# Buzzer_imp.net
KiCad netlist of a schematic drawn in EAGLE
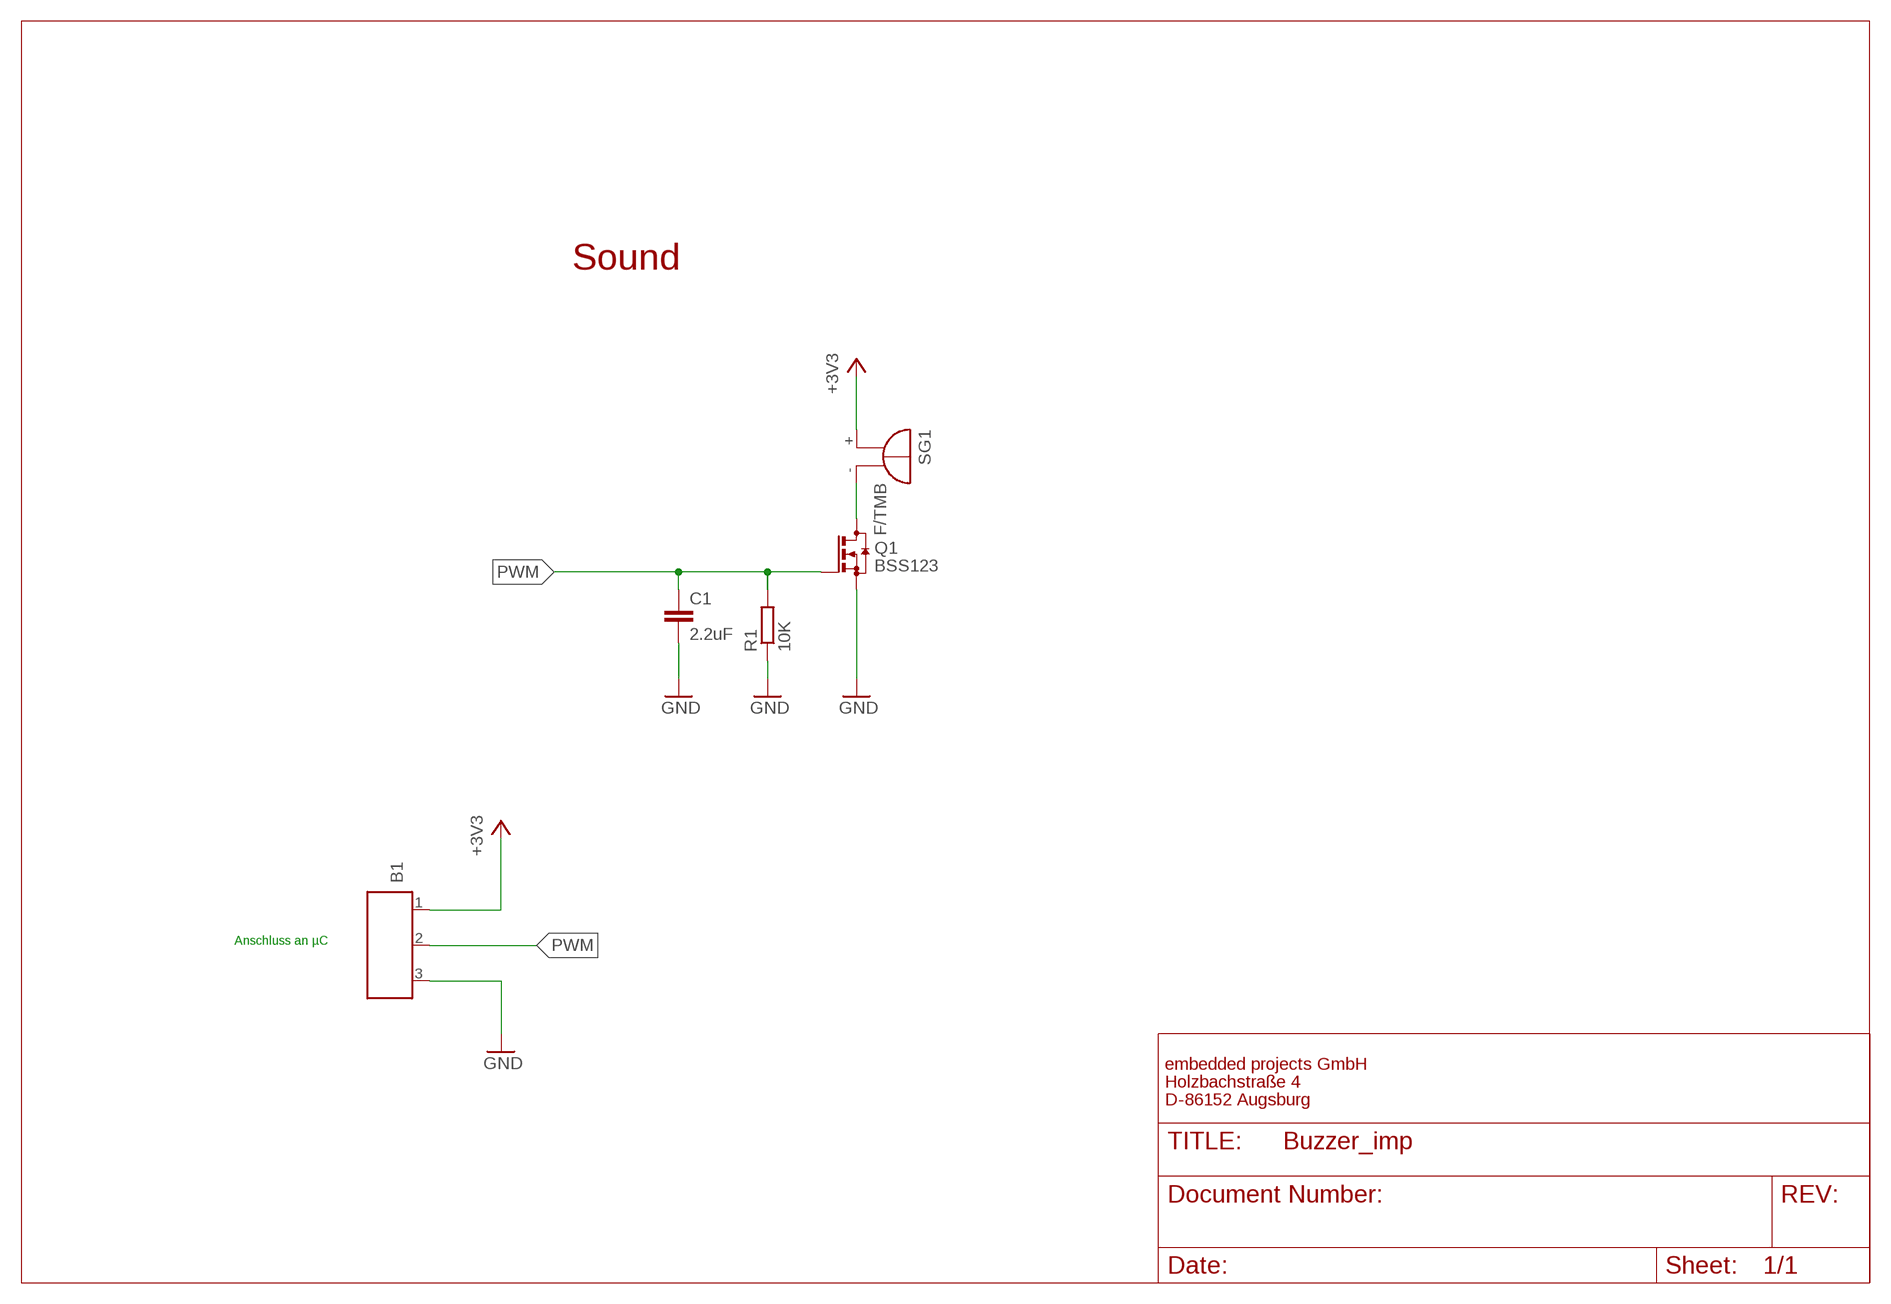
[diagram p0: schematic, sheet 1]

(export (version "E")
  (design (tool "Eeschema 10.0.6"))
  (components
    (comp (ref "B1")
      (value "MESSFUEHLER_3")
      (footprint "eagle-import:MESSFUEHLER_3")
      (libsource (lib "eagle-import") (part "MESSFUEHLER_3"))
    )
    (comp (ref "C1")
      (value "2.2uF")
      (footprint "eagle-import:C0805")
      (libsource (lib "eagle-import") (part "C-EUC0805"))
    )
    (comp (ref "Q1")
      (value "BSS123")
      (footprint "eagle-import:SOT-23")
      (libsource (lib "eagle-import") (part "BSS123"))
    )
    (comp (ref "R1")
      (value "10K")
      (footprint "eagle-import:R0805")
      (libsource (lib "eagle-import") (part "R-EU_R0805"))
    )
    (comp (ref "SG1")
      (value "F/TMB")
      (footprint "eagle-import:F_TMB")
      (libsource (lib "eagle-import") (part "F/TMB"))
    )
  )
  (nets
    (net (code "1") (name "+3V3") (class "Default")
      (node (ref "B1") (pin "1") (pinfunction "1_1") (pintype "passive"))
      (node (ref "SG1") (pin "+") (pinfunction "+_+") (pintype "passive"))
    )
    (net (code "2") (name "GND") (class "Default")
      (node (ref "B1") (pin "3") (pinfunction "3_3") (pintype "passive"))
      (node (ref "C1") (pin "2") (pinfunction "2_2") (pintype "passive"))
      (node (ref "Q1") (pin "2") (pinfunction "S_2") (pintype "passive"))
      (node (ref "R1") (pin "1") (pinfunction "1_1") (pintype "passive"))
    )
    (net (code "3") (name "Net-(Q1-D)") (class "Default")
      (node (ref "Q1") (pin "3") (pinfunction "D_3") (pintype "passive"))
      (node (ref "SG1") (pin "-") (pinfunction "-_-") (pintype "passive"))
    )
    (net (code "4") (name "PWM") (class "Default")
      (node (ref "B1") (pin "2") (pinfunction "2_2") (pintype "passive"))
      (node (ref "C1") (pin "1") (pinfunction "1_1") (pintype "passive"))
      (node (ref "Q1") (pin "1") (pinfunction "G_1") (pintype "passive"))
      (node (ref "R1") (pin "2") (pinfunction "2_2") (pintype "passive"))
    )
  )
)
